# envelope_detector.net
KiCad netlist of a schematic drawn in Altium Designer
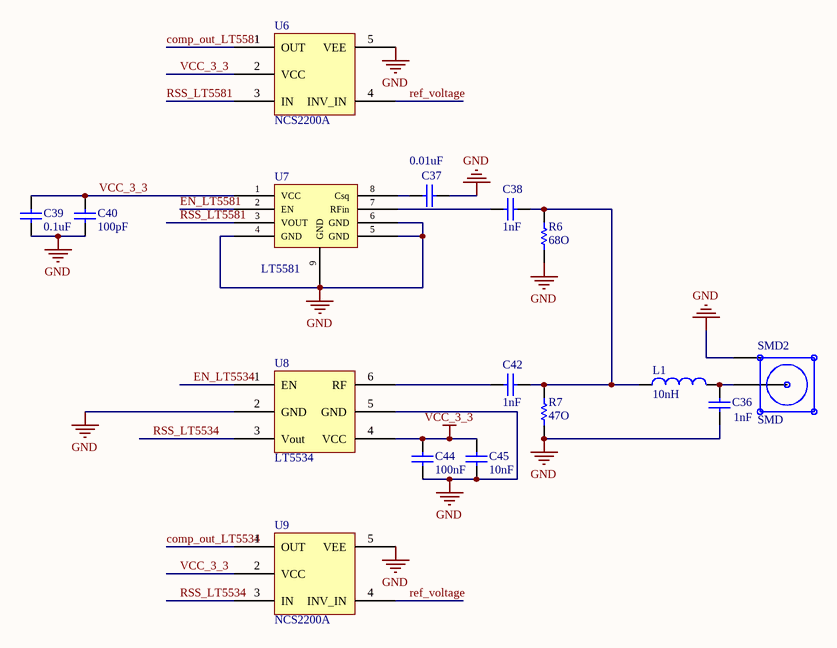
[diagram p0: envelope_detector.SchDoc]

(export (version "E")
  (design (tool "Eeschema 10.0.6"))
  (components
    (comp (ref "C36")
      (value "1nF")
      (footprint "0603")
      (description "Ceramic Capacitor (Surface Mount)")
      (fields (field (name "MANUFACTURER") "Generic Ceramic Chip Cap (TBD)") (field (name "Comment") "Cap"))
      (libsource (lib "wisp") (part "Cap"))
    )
    (comp (ref "C37")
      (value "0.01uF")
      (footprint "0603")
      (description "Ceramic Capacitor (Surface Mount)")
      (fields (field (name "MANUFACTURER") "Generic Ceramic Chip Cap (TBD)") (field (name "Comment") "Cap"))
      (libsource (lib "wisp") (part "Cap"))
    )
    (comp (ref "C38")
      (value "1nF")
      (footprint "0603")
      (description "Ceramic Capacitor (Surface Mount)")
      (fields (field (name "MANUFACTURER") "Generic Ceramic Chip Cap (TBD)") (field (name "Comment") "Cap"))
      (libsource (lib "wisp") (part "Cap"))
    )
    (comp (ref "C39")
      (value "0.1uF")
      (footprint "0603")
      (description "Ceramic Capacitor (Surface Mount)")
      (fields (field (name "MANUFACTURER") "Generic Ceramic Chip Cap (TBD)") (field (name "Comment") "Cap"))
      (libsource (lib "wisp") (part "Cap"))
    )
    (comp (ref "C40")
      (value "100pF")
      (footprint "0603")
      (description "Ceramic Capacitor (Surface Mount)")
      (fields (field (name "MANUFACTURER") "Generic Ceramic Chip Cap (TBD)") (field (name "Comment") "Cap"))
      (libsource (lib "wisp") (part "Cap"))
    )
    (comp (ref "C42")
      (value "1nF")
      (footprint "0603")
      (description "Ceramic Capacitor (Surface Mount)")
      (fields (field (name "MANUFACTURER") "Generic Ceramic Chip Cap (TBD)") (field (name "Comment") "Cap"))
      (libsource (lib "wisp") (part "Cap"))
    )
    (comp (ref "C44")
      (value "100nF")
      (footprint "0603")
      (description "Ceramic Capacitor (Surface Mount)")
      (fields (field (name "MANUFACTURER") "Generic Ceramic Chip Cap (TBD)") (field (name "Comment") "Cap"))
      (libsource (lib "wisp") (part "Cap"))
    )
    (comp (ref "C45")
      (value "10nF")
      (footprint "0603")
      (description "Ceramic Capacitor (Surface Mount)")
      (fields (field (name "MANUFACTURER") "Generic Ceramic Chip Cap (TBD)") (field (name "Comment") "Cap"))
      (libsource (lib "wisp") (part "Cap"))
    )
    (comp (ref "L1")
      (value "10nH")
      (footprint "0603")
      (description "Inductor (Surface Mount)")
      (fields (field (name "Comment") "Ind"))
      (libsource (lib "wisp") (part "Ind"))
    )
    (comp (ref "R6")
      (value "68O")
      (footprint "0603")
      (description "Chip Resistor (Surface Mount)")
      (fields (field (name "MANUFACTURER") "Generic Chip Res (TBD)") (field (name "Comment") "Res"))
      (libsource (lib "wisp") (part "Res"))
    )
    (comp (ref "R7")
      (value "47O")
      (footprint "0603")
      (description "Chip Resistor (Surface Mount)")
      (fields (field (name "MANUFACTURER") "Generic Chip Res (TBD)") (field (name "Comment") "Res"))
      (libsource (lib "wisp") (part "Res"))
    )
    (comp (ref "SMD2") (value "SMD") (footprint "SMD") (libsource (lib "pengyulib") (part "SMD")))
    (comp (ref "U6") (value "NCS2200A") (footprint "NCS2200") (libsource (lib "pengyulib") (part "NCS2200A")))
    (comp (ref "U7") (value "LT5581") (footprint "LT5581") (libsource (lib "pengyulib") (part "LT5581")))
    (comp (ref "U8") (value "LT5534") (footprint "LT5534") (libsource (lib "pengyulib") (part "LT5534")))
    (comp (ref "U9") (value "NCS2200A") (footprint "NCS2200") (libsource (lib "pengyulib") (part "NCS2200A")))
  )
  (nets
    (net (code "1") (name "/EN_LT5534") (class "Default")
      (node (ref "U8") (pin "1") (pinfunction "EN_1") (pintype "passive"))
    )
    (net (code "2") (name "/EN_LT5581") (class "Default")
      (node (ref "U7") (pin "2") (pinfunction "EN_2") (pintype "passive"))
    )
    (net (code "3") (name "/RSS_LT5534") (class "Default")
      (node (ref "U8") (pin "3") (pinfunction "Vout_3") (pintype "passive"))
      (node (ref "U9") (pin "3") (pinfunction "IN_3") (pintype "passive"))
    )
    (net (code "4") (name "/RSS_LT5581") (class "Default")
      (node (ref "U6") (pin "3") (pinfunction "IN_3") (pintype "passive"))
      (node (ref "U7") (pin "3") (pinfunction "VOUT_3") (pintype "passive"))
    )
    (net (code "5") (name "/comp_out_LT5534") (class "Default")
      (node (ref "U9") (pin "1") (pinfunction "OUT_1") (pintype "passive"))
    )
    (net (code "6") (name "/comp_out_LT5581") (class "Default")
      (node (ref "U6") (pin "1") (pinfunction "OUT_1") (pintype "passive"))
    )
    (net (code "7") (name "/ref_voltage") (class "Default")
      (node (ref "U6") (pin "4") (pinfunction "INV_IN_4") (pintype "passive"))
      (node (ref "U9") (pin "4") (pinfunction "INV_IN_4") (pintype "passive"))
    )
    (net (code "8") (name "GND") (class "Default")
      (node (ref "C36") (pin "1") (pinfunction "1_1") (pintype "passive"))
      (node (ref "C37") (pin "1") (pinfunction "1_1") (pintype "passive"))
      (node (ref "C39") (pin "1") (pinfunction "1_1") (pintype "passive"))
      (node (ref "C40") (pin "1") (pinfunction "1_1") (pintype "passive"))
      (node (ref "C44") (pin "1") (pinfunction "1_1") (pintype "passive"))
      (node (ref "C45") (pin "1") (pinfunction "1_1") (pintype "passive"))
      (node (ref "R6") (pin "1") (pinfunction "1_1") (pintype "passive"))
      (node (ref "R7") (pin "1") (pinfunction "1_1") (pintype "passive"))
      (node (ref "SMD2") (pin "1") (pinfunction "1_1") (pintype "passive"))
      (node (ref "U6") (pin "5") (pinfunction "VEE_5") (pintype "passive"))
      (node (ref "U7") (pin "4") (pinfunction "GND_4") (pintype "passive"))
      (node (ref "U7") (pin "5") (pinfunction "GND_5") (pintype "passive"))
      (node (ref "U7") (pin "6") (pinfunction "GND_6") (pintype "passive"))
      (node (ref "U7") (pin "9") (pinfunction "GND_9") (pintype "passive"))
      (node (ref "U8") (pin "2") (pinfunction "GND_2") (pintype "passive"))
      (node (ref "U8") (pin "5") (pinfunction "GND_5") (pintype "passive"))
      (node (ref "U9") (pin "5") (pinfunction "VEE_5") (pintype "passive"))
    )
    (net (code "9") (name "Net-(C36-Pad2)") (class "Default")
      (node (ref "C36") (pin "2") (pinfunction "2_2") (pintype "passive"))
      (node (ref "L1") (pin "2") (pinfunction "2_2") (pintype "passive"))
      (node (ref "SMD2") (pin "2") (pinfunction "2_2") (pintype "passive"))
    )
    (net (code "10") (name "Net-(C38-Pad2)") (class "Default")
      (node (ref "C38") (pin "2") (pinfunction "2_2") (pintype "passive"))
      (node (ref "C42") (pin "2") (pinfunction "2_2") (pintype "passive"))
      (node (ref "L1") (pin "1") (pinfunction "1_1") (pintype "passive"))
      (node (ref "R6") (pin "2") (pinfunction "2_2") (pintype "passive"))
      (node (ref "R7") (pin "2") (pinfunction "2_2") (pintype "passive"))
    )
    (net (code "11") (name "Net-(U7-Csq)") (class "Default")
      (node (ref "C37") (pin "2") (pinfunction "2_2") (pintype "passive"))
      (node (ref "U7") (pin "8") (pinfunction "Csq_8") (pintype "passive"))
    )
    (net (code "12") (name "Net-(U7-RFin)") (class "Default")
      (node (ref "C38") (pin "1") (pinfunction "1_1") (pintype "passive"))
      (node (ref "U7") (pin "7") (pinfunction "RFin_7") (pintype "passive"))
    )
    (net (code "13") (name "Net-(U8-RF)") (class "Default")
      (node (ref "C42") (pin "1") (pinfunction "1_1") (pintype "passive"))
      (node (ref "U8") (pin "6") (pinfunction "RF_6") (pintype "passive"))
    )
    (net (code "14") (name "VCC_3_3") (class "Default")
      (node (ref "C39") (pin "2") (pinfunction "2_2") (pintype "passive"))
      (node (ref "C40") (pin "2") (pinfunction "2_2") (pintype "passive"))
      (node (ref "C44") (pin "2") (pinfunction "2_2") (pintype "passive"))
      (node (ref "C45") (pin "2") (pinfunction "2_2") (pintype "passive"))
      (node (ref "U6") (pin "2") (pinfunction "VCC_2") (pintype "passive"))
      (node (ref "U7") (pin "1") (pinfunction "VCC_1") (pintype "passive"))
      (node (ref "U8") (pin "4") (pinfunction "VCC_4") (pintype "passive"))
      (node (ref "U9") (pin "2") (pinfunction "VCC_2") (pintype "passive"))
    )
  )
)
